# CPLD44.net
KiCad netlist of a schematic drawn in EAGLE
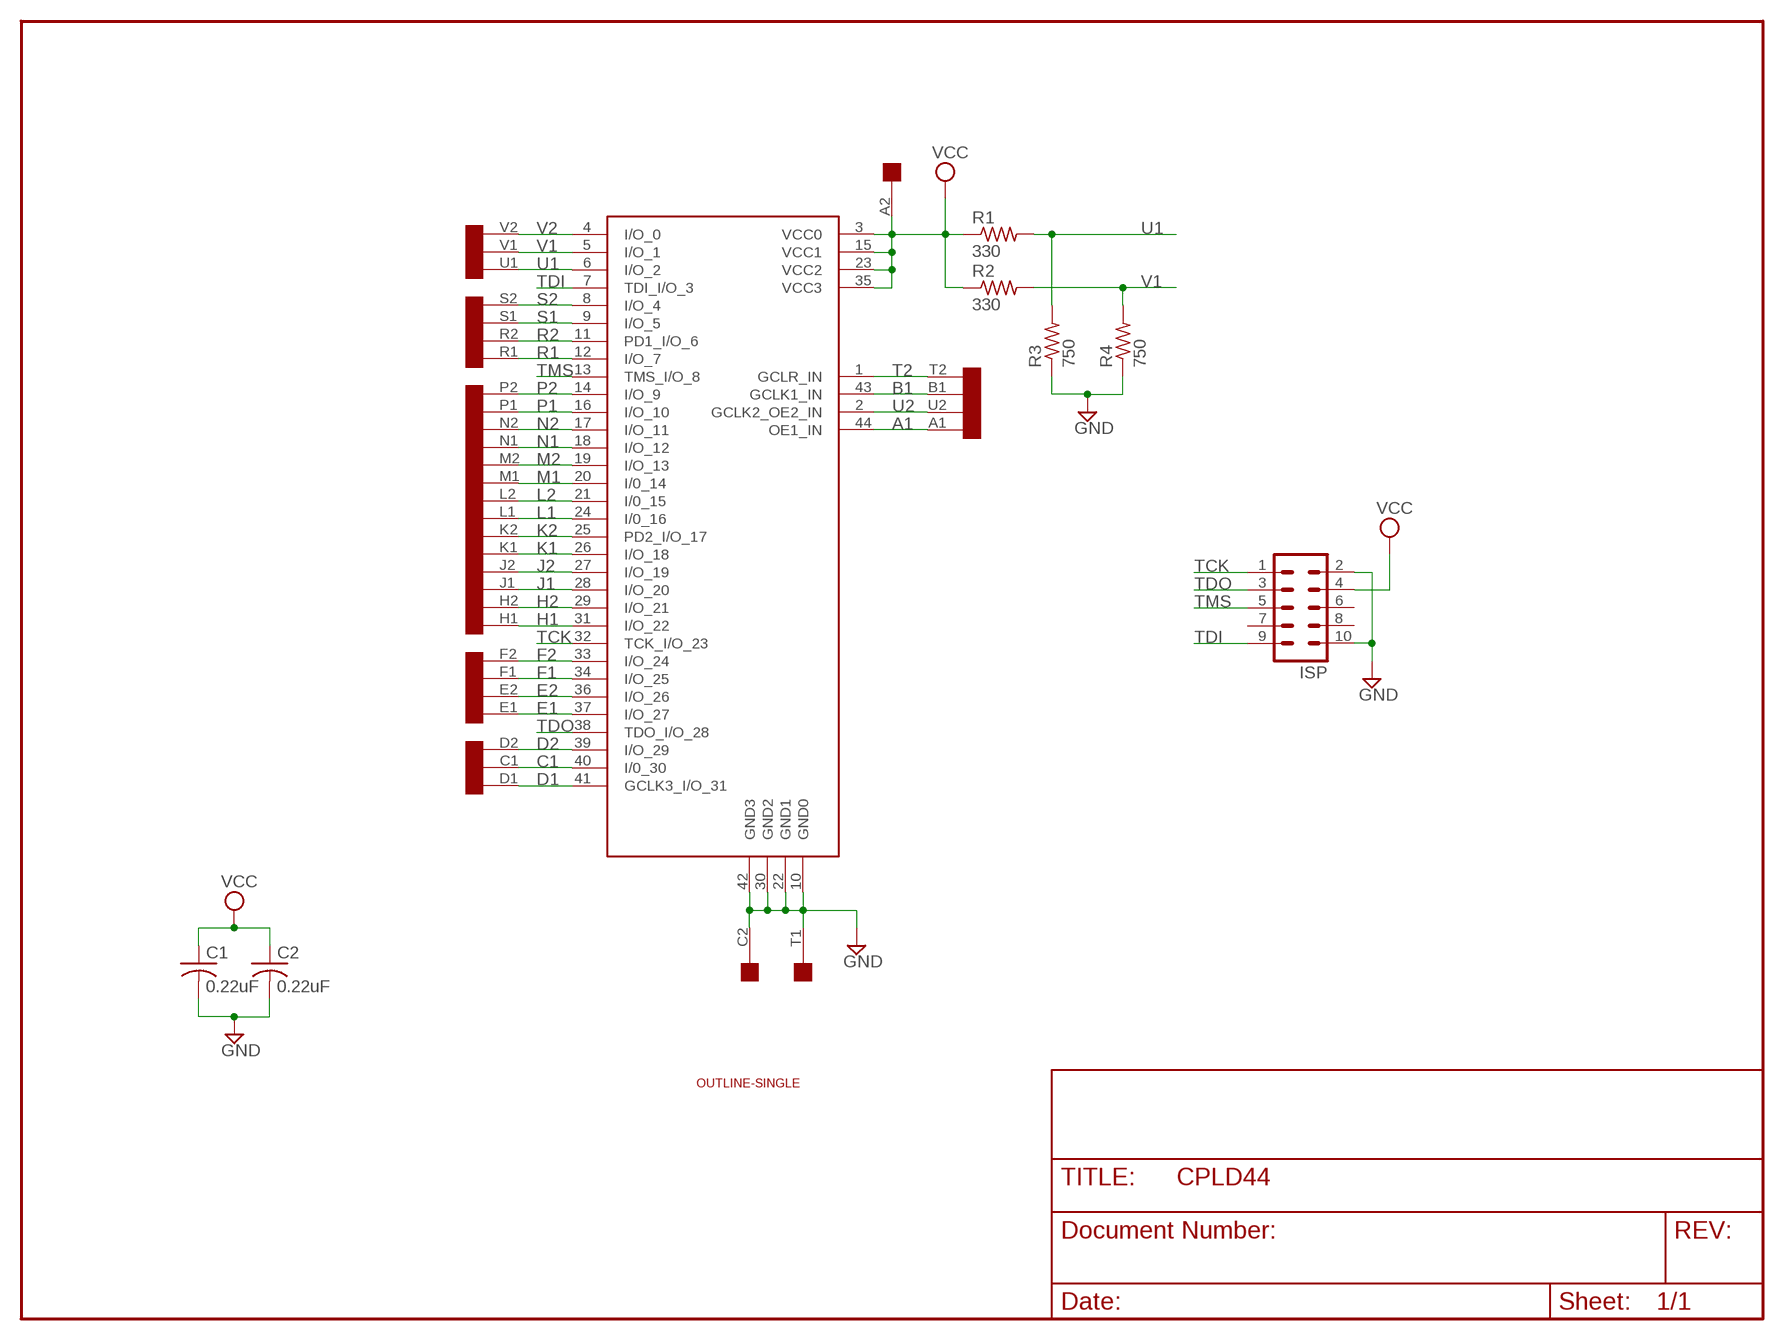
[diagram p0: schematic, sheet 1]

(export (version "E")
  (design (tool "Eeschema 10.0.6"))
  (components
    (comp (ref "C1")
      (value "0.22uF")
      (footprint "eagle-import:C050-025X075")
      (libsource (lib "eagle-import") (part "C-US050-025X075"))
    )
    (comp (ref "C2")
      (value "0.22uF")
      (footprint "eagle-import:C050-025X075")
      (libsource (lib "eagle-import") (part "C-US050-025X075"))
    )
    (comp (ref "E1")
      (value "ATF1502PLCC44")
      (footprint "eagle-import:3M44")
      (libsource (lib "eagle-import") (part "ATF1502PLCC44"))
    )
    (comp (ref "ISP")
      (value "MA05-2")
      (footprint "eagle-import:MA05-2")
      (libsource (lib "eagle-import") (part "MA05-2"))
    )
    (comp (ref "R1")
      (value "330")
      (footprint "eagle-import:0207_10")
      (libsource (lib "eagle-import") (part "R-US_0207/10"))
    )
    (comp (ref "R2")
      (value "330")
      (footprint "eagle-import:0207_10")
      (libsource (lib "eagle-import") (part "R-US_0207/10"))
    )
    (comp (ref "R3")
      (value "750")
      (footprint "eagle-import:0207_10")
      (libsource (lib "eagle-import") (part "R-US_0207/10"))
    )
    (comp (ref "R4")
      (value "750")
      (footprint "eagle-import:0207_10")
      (libsource (lib "eagle-import") (part "R-US_0207/10"))
    )
    (comp (ref "U$1")
      (value "SINGLE")
      (footprint "eagle-import:EDGE-CON2")
      (libsource (lib "eagle-import") (part "SINGLE"))
    )
    (comp (ref "U$3")
      (value "OUTLINE-SINGLE")
      (footprint "eagle-import:SINGLE")
      (libsource (lib "eagle-import") (part "OUTLINE-SINGLE"))
    )
  )
  (nets
    (net (code "1") (name "/A1") (class "Default")
      (node (ref "E1") (pin "44") (pinfunction "OE1_IN_44") (pintype "bidirectional"))
      (node (ref "U$1") (pin "A1") (pinfunction "1_A1") (pintype "bidirectional"))
    )
    (net (code "2") (name "/B1") (class "Default")
      (node (ref "E1") (pin "43") (pinfunction "GCLK1_IN_43") (pintype "bidirectional"))
      (node (ref "U$1") (pin "B1") (pinfunction "1_B1") (pintype "bidirectional"))
    )
    (net (code "3") (name "/C1") (class "Default")
      (node (ref "E1") (pin "40") (pinfunction "I/0_30_40") (pintype "bidirectional"))
      (node (ref "U$1") (pin "C1") (pinfunction "1_C1") (pintype "bidirectional"))
    )
    (net (code "4") (name "/D1") (class "Default")
      (node (ref "E1") (pin "41") (pinfunction "GCLK3_I/O_31_41") (pintype "bidirectional"))
      (node (ref "U$1") (pin "D1") (pinfunction "1_D1") (pintype "bidirectional"))
    )
    (net (code "5") (name "/D2") (class "Default")
      (node (ref "E1") (pin "39") (pinfunction "I/O_29_39") (pintype "bidirectional"))
      (node (ref "U$1") (pin "D2") (pinfunction "1_D2") (pintype "bidirectional"))
    )
    (net (code "6") (name "/E1") (class "Default")
      (node (ref "E1") (pin "37") (pinfunction "I/O_27_37") (pintype "bidirectional"))
      (node (ref "U$1") (pin "E1") (pinfunction "1_E1") (pintype "bidirectional"))
    )
    (net (code "7") (name "/E2") (class "Default")
      (node (ref "E1") (pin "36") (pinfunction "I/O_26_36") (pintype "bidirectional"))
      (node (ref "U$1") (pin "E2") (pinfunction "1_E2") (pintype "bidirectional"))
    )
    (net (code "8") (name "/F1") (class "Default")
      (node (ref "E1") (pin "34") (pinfunction "I/O_25_34") (pintype "bidirectional"))
      (node (ref "U$1") (pin "F1") (pinfunction "1_F1") (pintype "bidirectional"))
    )
    (net (code "9") (name "/F2") (class "Default")
      (node (ref "E1") (pin "33") (pinfunction "I/O_24_33") (pintype "bidirectional"))
      (node (ref "U$1") (pin "F2") (pinfunction "1_F2") (pintype "bidirectional"))
    )
    (net (code "10") (name "/H1") (class "Default")
      (node (ref "E1") (pin "31") (pinfunction "I/O_22_31") (pintype "bidirectional"))
      (node (ref "U$1") (pin "H1") (pinfunction "1_H1") (pintype "bidirectional"))
    )
    (net (code "11") (name "/H2") (class "Default")
      (node (ref "E1") (pin "29") (pinfunction "I/O_21_29") (pintype "bidirectional"))
      (node (ref "U$1") (pin "H2") (pinfunction "1_H2") (pintype "bidirectional"))
    )
    (net (code "12") (name "/J1") (class "Default")
      (node (ref "E1") (pin "28") (pinfunction "I/O_20_28") (pintype "bidirectional"))
      (node (ref "U$1") (pin "J1") (pinfunction "1_J1") (pintype "bidirectional"))
    )
    (net (code "13") (name "/J2") (class "Default")
      (node (ref "E1") (pin "27") (pinfunction "I/O_19_27") (pintype "bidirectional"))
      (node (ref "U$1") (pin "J2") (pinfunction "1_J2") (pintype "bidirectional"))
    )
    (net (code "14") (name "/K1") (class "Default")
      (node (ref "E1") (pin "26") (pinfunction "I/O_18_26") (pintype "bidirectional"))
      (node (ref "U$1") (pin "K1") (pinfunction "1_K1") (pintype "bidirectional"))
    )
    (net (code "15") (name "/K2") (class "Default")
      (node (ref "E1") (pin "25") (pinfunction "PD2_I/O_17_25") (pintype "bidirectional"))
      (node (ref "U$1") (pin "K2") (pinfunction "1_K2") (pintype "bidirectional"))
    )
    (net (code "16") (name "/L1") (class "Default")
      (node (ref "E1") (pin "24") (pinfunction "I/0_16_24") (pintype "bidirectional"))
      (node (ref "U$1") (pin "L1") (pinfunction "1_L1") (pintype "bidirectional"))
    )
    (net (code "17") (name "/L2") (class "Default")
      (node (ref "E1") (pin "21") (pinfunction "I/0_15_21") (pintype "bidirectional"))
      (node (ref "U$1") (pin "L2") (pinfunction "1_L2") (pintype "bidirectional"))
    )
    (net (code "18") (name "/M1") (class "Default")
      (node (ref "E1") (pin "20") (pinfunction "I/0_14_20") (pintype "bidirectional"))
      (node (ref "U$1") (pin "M1") (pinfunction "1_M1") (pintype "bidirectional"))
    )
    (net (code "19") (name "/M2") (class "Default")
      (node (ref "E1") (pin "19") (pinfunction "I/O_13_19") (pintype "bidirectional"))
      (node (ref "U$1") (pin "M2") (pinfunction "1_M2") (pintype "bidirectional"))
    )
    (net (code "20") (name "/N1") (class "Default")
      (node (ref "E1") (pin "18") (pinfunction "I/O_12_18") (pintype "bidirectional"))
      (node (ref "U$1") (pin "N1") (pinfunction "1_N1") (pintype "bidirectional"))
    )
    (net (code "21") (name "/N2") (class "Default")
      (node (ref "E1") (pin "17") (pinfunction "I/O_11_17") (pintype "bidirectional"))
      (node (ref "U$1") (pin "N2") (pinfunction "1_N2") (pintype "bidirectional"))
    )
    (net (code "22") (name "/P1") (class "Default")
      (node (ref "E1") (pin "16") (pinfunction "I/O_10_16") (pintype "bidirectional"))
      (node (ref "U$1") (pin "P1") (pinfunction "1_P1") (pintype "bidirectional"))
    )
    (net (code "23") (name "/P2") (class "Default")
      (node (ref "E1") (pin "14") (pinfunction "I/O_9_14") (pintype "bidirectional"))
      (node (ref "U$1") (pin "P2") (pinfunction "1_P2") (pintype "bidirectional"))
    )
    (net (code "24") (name "/R1") (class "Default")
      (node (ref "E1") (pin "12") (pinfunction "I/O_7_12") (pintype "bidirectional"))
      (node (ref "U$1") (pin "R1") (pinfunction "1_R1") (pintype "bidirectional"))
    )
    (net (code "25") (name "/R2") (class "Default")
      (node (ref "E1") (pin "11") (pinfunction "PD1_I/O_6_11") (pintype "bidirectional"))
      (node (ref "U$1") (pin "R2") (pinfunction "1_R2") (pintype "bidirectional"))
    )
    (net (code "26") (name "/S1") (class "Default")
      (node (ref "E1") (pin "9") (pinfunction "I/O_5_9") (pintype "bidirectional"))
      (node (ref "U$1") (pin "S1") (pinfunction "1_S1") (pintype "bidirectional"))
    )
    (net (code "27") (name "/S2") (class "Default")
      (node (ref "E1") (pin "8") (pinfunction "I/O_4_8") (pintype "bidirectional"))
      (node (ref "U$1") (pin "S2") (pinfunction "1_S2") (pintype "bidirectional"))
    )
    (net (code "28") (name "/T2") (class "Default")
      (node (ref "E1") (pin "1") (pinfunction "GCLR_IN_1") (pintype "bidirectional"))
      (node (ref "U$1") (pin "T2") (pinfunction "1_T2") (pintype "bidirectional"))
    )
    (net (code "29") (name "/TCK") (class "Default")
      (node (ref "E1") (pin "32") (pinfunction "TCK_I/O_23_32") (pintype "bidirectional"))
      (node (ref "ISP") (pin "1") (pinfunction "1_1") (pintype "passive"))
    )
    (net (code "30") (name "/TDI") (class "Default")
      (node (ref "E1") (pin "7") (pinfunction "TDI_I/O_3_7") (pintype "bidirectional"))
      (node (ref "ISP") (pin "9") (pinfunction "9_9") (pintype "passive"))
    )
    (net (code "31") (name "/TDO") (class "Default")
      (node (ref "E1") (pin "38") (pinfunction "TDO_I/O_28_38") (pintype "bidirectional"))
      (node (ref "ISP") (pin "3") (pinfunction "3_3") (pintype "passive"))
    )
    (net (code "32") (name "/TMS") (class "Default")
      (node (ref "E1") (pin "13") (pinfunction "TMS_I/O_8_13") (pintype "bidirectional"))
      (node (ref "ISP") (pin "5") (pinfunction "5_5") (pintype "passive"))
    )
    (net (code "33") (name "/U1") (class "Default")
      (node (ref "E1") (pin "6") (pinfunction "I/O_2_6") (pintype "bidirectional"))
      (node (ref "R1") (pin "2") (pinfunction "2_2") (pintype "passive"))
      (node (ref "R3") (pin "2") (pinfunction "2_2") (pintype "passive"))
      (node (ref "U$1") (pin "U1") (pinfunction "1_U1") (pintype "bidirectional"))
    )
    (net (code "34") (name "/U2") (class "Default")
      (node (ref "E1") (pin "2") (pinfunction "GCLK2_OE2_IN_2") (pintype "bidirectional"))
      (node (ref "U$1") (pin "U2") (pinfunction "1_U2") (pintype "bidirectional"))
    )
    (net (code "35") (name "/V1") (class "Default")
      (node (ref "E1") (pin "5") (pinfunction "I/O_1_5") (pintype "bidirectional"))
      (node (ref "R2") (pin "2") (pinfunction "2_2") (pintype "passive"))
      (node (ref "R4") (pin "2") (pinfunction "2_2") (pintype "passive"))
      (node (ref "U$1") (pin "V1") (pinfunction "1_V1") (pintype "bidirectional"))
    )
    (net (code "36") (name "/V2") (class "Default")
      (node (ref "E1") (pin "4") (pinfunction "I/O_0_4") (pintype "bidirectional"))
      (node (ref "U$1") (pin "V2") (pinfunction "1_V2") (pintype "bidirectional"))
    )
    (net (code "37") (name "GND") (class "Default")
      (node (ref "C1") (pin "2") (pinfunction "2_2") (pintype "passive"))
      (node (ref "C2") (pin "2") (pinfunction "2_2") (pintype "passive"))
      (node (ref "E1") (pin "10") (pinfunction "GND0_10") (pintype "bidirectional"))
      (node (ref "E1") (pin "22") (pinfunction "GND1_22") (pintype "bidirectional"))
      (node (ref "E1") (pin "30") (pinfunction "GND2_30") (pintype "bidirectional"))
      (node (ref "E1") (pin "42") (pinfunction "GND3_42") (pintype "bidirectional"))
      (node (ref "ISP") (pin "10") (pinfunction "10_10") (pintype "passive"))
      (node (ref "ISP") (pin "2") (pinfunction "2_2") (pintype "passive"))
      (node (ref "R3") (pin "1") (pinfunction "1_1") (pintype "passive"))
      (node (ref "R4") (pin "1") (pinfunction "1_1") (pintype "passive"))
      (node (ref "U$1") (pin "C2") (pinfunction "1_C2") (pintype "bidirectional"))
      (node (ref "U$1") (pin "T1") (pinfunction "1_T1") (pintype "bidirectional"))
    )
    (net (code "38") (name "VCC") (class "Default")
      (node (ref "C1") (pin "1") (pinfunction "1_1") (pintype "passive"))
      (node (ref "C2") (pin "1") (pinfunction "1_1") (pintype "passive"))
      (node (ref "E1") (pin "15") (pinfunction "VCC1_15") (pintype "bidirectional"))
      (node (ref "E1") (pin "23") (pinfunction "VCC2_23") (pintype "bidirectional"))
      (node (ref "E1") (pin "3") (pinfunction "VCC0_3") (pintype "bidirectional"))
      (node (ref "E1") (pin "35") (pinfunction "VCC3_35") (pintype "bidirectional"))
      (node (ref "ISP") (pin "4") (pinfunction "4_4") (pintype "passive"))
      (node (ref "R1") (pin "1") (pinfunction "1_1") (pintype "passive"))
      (node (ref "R2") (pin "1") (pinfunction "1_1") (pintype "passive"))
      (node (ref "U$1") (pin "A2") (pinfunction "1_A2") (pintype "bidirectional"))
    )
    (net (code "39") (name "unconnected-(ISP-Pad6)") (class "Default")
      (node (ref "ISP") (pin "6") (pinfunction "6_6") (pintype "passive"))
    )
    (net (code "40") (name "unconnected-(ISP-Pad7)") (class "Default")
      (node (ref "ISP") (pin "7") (pinfunction "7_7") (pintype "passive"))
    )
    (net (code "41") (name "unconnected-(ISP-Pad8)") (class "Default")
      (node (ref "ISP") (pin "8") (pinfunction "8_8") (pintype "passive"))
    )
  )
)
